# PotenciometersBoard.net
KiCad netlist of a schematic drawn in EAGLE
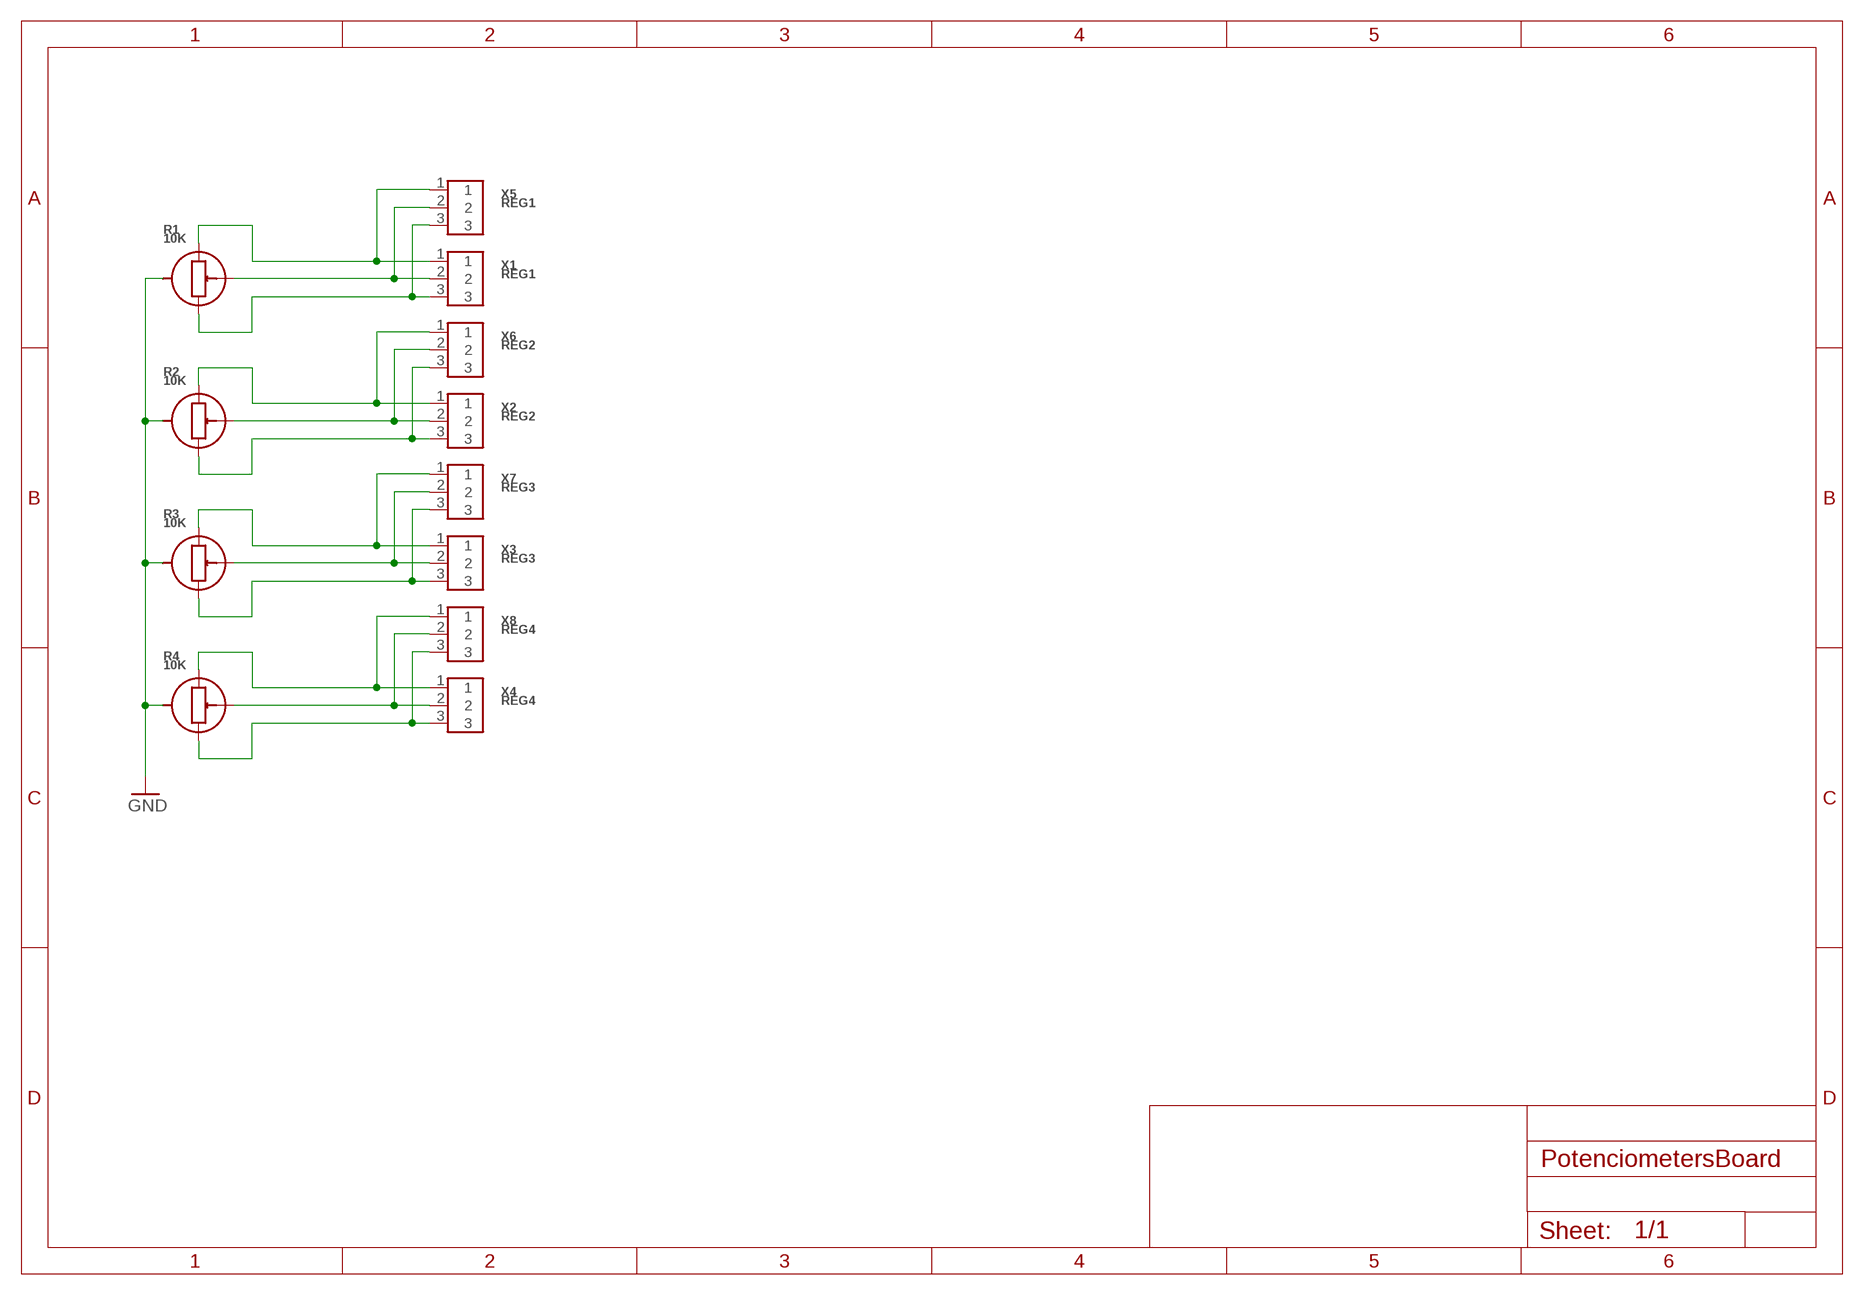
[diagram p0: schematic, sheet 1]

(export (version "E")
  (design (tool "Eeschema 10.0.6"))
  (components
    (comp (ref "R1")
      (value "10K")
      (footprint "eagle-import:SP3-4AM")
      (libsource (lib "eagle-import") (part "R_ADJ_WITH_SHIELDSP4-AM"))
    )
    (comp (ref "R2")
      (value "10K")
      (footprint "eagle-import:SP3-4AM")
      (libsource (lib "eagle-import") (part "R_ADJ_WITH_SHIELDSP4-AM"))
    )
    (comp (ref "R3")
      (value "10K")
      (footprint "eagle-import:SP3-4AM")
      (libsource (lib "eagle-import") (part "R_ADJ_WITH_SHIELDSP4-AM"))
    )
    (comp (ref "R4")
      (value "10K")
      (footprint "eagle-import:SP3-4AM")
      (libsource (lib "eagle-import") (part "R_ADJ_WITH_SHIELDSP4-AM"))
    )
    (comp (ref "X1")
      (value "REG1")
      (footprint "eagle-import:PIN3X1_2.54MM_WITH_CLAMP")
      (libsource (lib "eagle-import") (part "PIN1X3(2.54MM_WITH_CLAMP)"))
    )
    (comp (ref "X2")
      (value "REG2")
      (footprint "eagle-import:PIN3X1_2.54MM_WITH_CLAMP")
      (libsource (lib "eagle-import") (part "PIN1X3(2.54MM_WITH_CLAMP)"))
    )
    (comp (ref "X3")
      (value "REG3")
      (footprint "eagle-import:PIN3X1_2.54MM_WITH_CLAMP")
      (libsource (lib "eagle-import") (part "PIN1X3(2.54MM_WITH_CLAMP)"))
    )
    (comp (ref "X4")
      (value "REG4")
      (footprint "eagle-import:PIN3X1_2.54MM_WITH_CLAMP")
      (libsource (lib "eagle-import") (part "PIN1X3(2.54MM_WITH_CLAMP)"))
    )
    (comp (ref "X5")
      (value "REG1")
      (footprint "eagle-import:PIN1X3_2.54MM_SIDE_BOARD")
      (libsource (lib "eagle-import") (part "PIN1X3(2.54MM_SIDE_BOARD)"))
    )
    (comp (ref "X6")
      (value "REG2")
      (footprint "eagle-import:PIN1X3_2.54MM_SIDE_BOARD")
      (libsource (lib "eagle-import") (part "PIN1X3(2.54MM_SIDE_BOARD)"))
    )
    (comp (ref "X7")
      (value "REG3")
      (footprint "eagle-import:PIN1X3_2.54MM_SIDE_BOARD")
      (libsource (lib "eagle-import") (part "PIN1X3(2.54MM_SIDE_BOARD)"))
    )
    (comp (ref "X8")
      (value "REG4")
      (footprint "eagle-import:PIN1X3_2.54MM_SIDE_BOARD")
      (libsource (lib "eagle-import") (part "PIN1X3(2.54MM_SIDE_BOARD)"))
    )
  )
  (nets
    (net (code "1") (name "GND") (class "Default")
      (node (ref "R1") (pin "PACKAGE1") (pinfunction "PACKAGE_PACKAGE1") (pintype "bidirectional"))
      (node (ref "R1") (pin "PACKAGE2") (pinfunction "PACKAGE_PACKAGE2") (pintype "bidirectional"))
      (node (ref "R2") (pin "PACKAGE1") (pinfunction "PACKAGE_PACKAGE1") (pintype "bidirectional"))
      (node (ref "R2") (pin "PACKAGE2") (pinfunction "PACKAGE_PACKAGE2") (pintype "bidirectional"))
      (node (ref "R3") (pin "PACKAGE1") (pinfunction "PACKAGE_PACKAGE1") (pintype "bidirectional"))
      (node (ref "R3") (pin "PACKAGE2") (pinfunction "PACKAGE_PACKAGE2") (pintype "bidirectional"))
      (node (ref "R4") (pin "PACKAGE1") (pinfunction "PACKAGE_PACKAGE1") (pintype "bidirectional"))
      (node (ref "R4") (pin "PACKAGE2") (pinfunction "PACKAGE_PACKAGE2") (pintype "bidirectional"))
    )
    (net (code "2") (name "Net-(R1-PadEND_A)") (class "Default")
      (node (ref "R1") (pin "END_A") (pinfunction "END_A_END_A") (pintype "passive"))
      (node (ref "X1") (pin "3") (pinfunction "3_3") (pintype "passive"))
      (node (ref "X5") (pin "3") (pinfunction "3_3") (pintype "passive"))
    )
    (net (code "3") (name "Net-(R1-PadEND_B)") (class "Default")
      (node (ref "R1") (pin "END_B") (pinfunction "END_B_END_B") (pintype "passive"))
      (node (ref "X1") (pin "1") (pinfunction "1_1") (pintype "passive"))
      (node (ref "X5") (pin "1") (pinfunction "1_1") (pintype "passive"))
    )
    (net (code "4") (name "Net-(R1-PadMIDDLE)") (class "Default")
      (node (ref "R1") (pin "MIDDLE") (pinfunction "MIDDLE_MIDDLE") (pintype "passive"))
      (node (ref "X1") (pin "2") (pinfunction "2_2") (pintype "passive"))
      (node (ref "X5") (pin "2") (pinfunction "2_2") (pintype "passive"))
    )
    (net (code "5") (name "Net-(R2-PadEND_A)") (class "Default")
      (node (ref "R2") (pin "END_A") (pinfunction "END_A_END_A") (pintype "passive"))
      (node (ref "X2") (pin "3") (pinfunction "3_3") (pintype "passive"))
      (node (ref "X6") (pin "3") (pinfunction "3_3") (pintype "passive"))
    )
    (net (code "6") (name "Net-(R2-PadEND_B)") (class "Default")
      (node (ref "R2") (pin "END_B") (pinfunction "END_B_END_B") (pintype "passive"))
      (node (ref "X2") (pin "1") (pinfunction "1_1") (pintype "passive"))
      (node (ref "X6") (pin "1") (pinfunction "1_1") (pintype "passive"))
    )
    (net (code "7") (name "Net-(R2-PadMIDDLE)") (class "Default")
      (node (ref "R2") (pin "MIDDLE") (pinfunction "MIDDLE_MIDDLE") (pintype "passive"))
      (node (ref "X2") (pin "2") (pinfunction "2_2") (pintype "passive"))
      (node (ref "X6") (pin "2") (pinfunction "2_2") (pintype "passive"))
    )
    (net (code "8") (name "Net-(R3-PadEND_A)") (class "Default")
      (node (ref "R3") (pin "END_A") (pinfunction "END_A_END_A") (pintype "passive"))
      (node (ref "X3") (pin "3") (pinfunction "3_3") (pintype "passive"))
      (node (ref "X7") (pin "3") (pinfunction "3_3") (pintype "passive"))
    )
    (net (code "9") (name "Net-(R3-PadEND_B)") (class "Default")
      (node (ref "R3") (pin "END_B") (pinfunction "END_B_END_B") (pintype "passive"))
      (node (ref "X3") (pin "1") (pinfunction "1_1") (pintype "passive"))
      (node (ref "X7") (pin "1") (pinfunction "1_1") (pintype "passive"))
    )
    (net (code "10") (name "Net-(R3-PadMIDDLE)") (class "Default")
      (node (ref "R3") (pin "MIDDLE") (pinfunction "MIDDLE_MIDDLE") (pintype "passive"))
      (node (ref "X3") (pin "2") (pinfunction "2_2") (pintype "passive"))
      (node (ref "X7") (pin "2") (pinfunction "2_2") (pintype "passive"))
    )
    (net (code "11") (name "Net-(R4-PadEND_A)") (class "Default")
      (node (ref "R4") (pin "END_A") (pinfunction "END_A_END_A") (pintype "passive"))
      (node (ref "X4") (pin "3") (pinfunction "3_3") (pintype "passive"))
      (node (ref "X8") (pin "3") (pinfunction "3_3") (pintype "passive"))
    )
    (net (code "12") (name "Net-(R4-PadEND_B)") (class "Default")
      (node (ref "R4") (pin "END_B") (pinfunction "END_B_END_B") (pintype "passive"))
      (node (ref "X4") (pin "1") (pinfunction "1_1") (pintype "passive"))
      (node (ref "X8") (pin "1") (pinfunction "1_1") (pintype "passive"))
    )
    (net (code "13") (name "Net-(R4-PadMIDDLE)") (class "Default")
      (node (ref "R4") (pin "MIDDLE") (pinfunction "MIDDLE_MIDDLE") (pintype "passive"))
      (node (ref "X4") (pin "2") (pinfunction "2_2") (pintype "passive"))
      (node (ref "X8") (pin "2") (pinfunction "2_2") (pintype "passive"))
    )
  )
)
